# deepshark_power_sch.net
KiCad netlist of a schematic drawn in Altium Designer
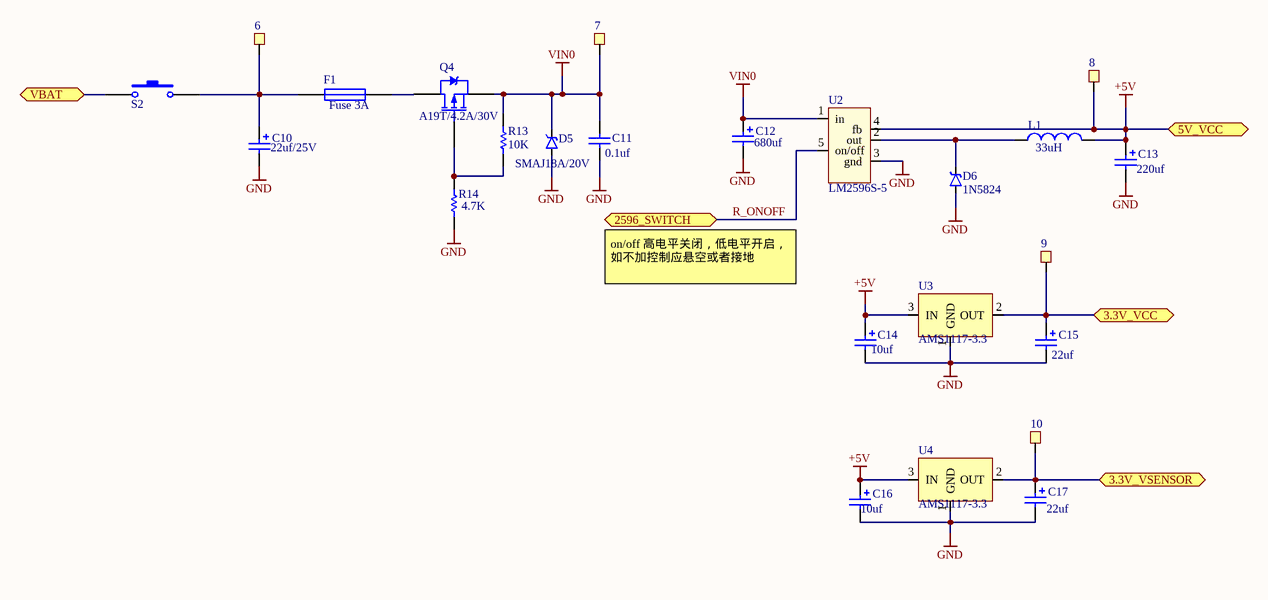
[diagram p0: deepshark_power_sch.SchDoc]

(export (version "E")
  (design (tool "Eeschema 10.0.6"))
  (components
    (comp (ref "6") (value "TP") (footprint "TestPoint") (libsource (lib "deepshark_sch_lib") (part "TP")))
    (comp (ref "7") (value "TP") (footprint "TestPoint") (libsource (lib "deepshark_sch_lib") (part "TP")))
    (comp (ref "8") (value "TP") (footprint "TestPoint") (libsource (lib "deepshark_sch_lib") (part "TP")))
    (comp (ref "9") (value "TP") (footprint "TestPoint") (libsource (lib "deepshark_sch_lib") (part "TP")))
    (comp (ref "10") (value "TP") (footprint "TestPoint") (libsource (lib "deepshark_sch_lib") (part "TP")))
    (comp (ref "C10")
      (value "22uf/25V")
      (footprint "22uf-25V")
      (description "Polarized Capacitor (Axial)")
      (fields (field (name "Comment") "Cap Pol2") (field (name "PUBLISHER") "Altium Limited"))
      (libsource (lib "Miscellaneous Devices") (part "Cap Pol2"))
    )
    (comp (ref "C11")
      (value "0.1uf")
      (footprint "6-0805_M")
      (description "Capacitor")
      (fields (field (name "Comment") "Cap") (field (name "PUBLISHER") "Altium Limited"))
      (libsource (lib "Miscellaneous Devices") (part "Cap"))
    )
    (comp (ref "C12")
      (value "680uf")
      (footprint "680uf-50v")
      (description "Polarized Capacitor (Axial)")
      (fields (field (name "Comment") "Cap Pol2") (field (name "PUBLISHER") "Altium Limited"))
      (libsource (lib "Miscellaneous Devices") (part "Cap Pol2"))
    )
    (comp (ref "C13")
      (value "220uf")
      (footprint "220uf-50v")
      (description "Polarized Capacitor (Axial)")
      (fields (field (name "Comment") "Cap Pol2") (field (name "PUBLISHER") "Altium Limited"))
      (libsource (lib "Miscellaneous Devices") (part "Cap Pol2"))
    )
    (comp (ref "C14")
      (value "10uf")
      (footprint "1206")
      (description "Polarized Capacitor (Axial)")
      (fields (field (name "Comment") "Cap Pol2") (field (name "PUBLISHER") "Altium Limited"))
      (libsource (lib "Miscellaneous Devices") (part "Cap Pol2"))
    )
    (comp (ref "C15")
      (value "22uf")
      (footprint "my0603")
      (description "Polarized Capacitor (Axial)")
      (fields (field (name "Comment") "Cap Pol2") (field (name "PUBLISHER") "Altium Limited"))
      (libsource (lib "Miscellaneous Devices") (part "Cap Pol2"))
    )
    (comp (ref "C16")
      (value "10uf")
      (footprint "1206")
      (description "Polarized Capacitor (Axial)")
      (fields (field (name "Comment") "Cap Pol2") (field (name "PUBLISHER") "Altium Limited"))
      (libsource (lib "Miscellaneous Devices") (part "Cap Pol2"))
    )
    (comp (ref "C17")
      (value "22uf")
      (footprint "my0603")
      (description "Polarized Capacitor (Axial)")
      (fields (field (name "Comment") "Cap Pol2") (field (name "PUBLISHER") "Altium Limited"))
      (libsource (lib "Miscellaneous Devices") (part "Cap Pol2"))
    )
    (comp (ref "D5") (value "SMAJ18A/20V") (footprint "SMBJ6.5A") (libsource (lib "常用2") (part "DW")))
    (comp (ref "D6") (value "1N5824") (footprint "1N5824") (libsource (lib "常用2") (part "DW")))
    (comp (ref "F1")
      (value "Fuse 3A")
      (footprint "1206")
      (description "Fuse")
      (fields (field (name "PUBLISHER") "Altium Limited"))
      (libsource (lib "Miscellaneous Devices") (part "Fuse 1"))
    )
    (comp (ref "L1")
      (value "33uH")
      (footprint "12x12 L")
      (description "Inductor")
      (fields (field (name "PUBLISHER") "Altium Limited"))
      (libsource (lib "Miscellaneous Devices") (part "Inductor"))
    )
    (comp (ref "Q4")
      (value "A19T/4.2A/30V")
      (footprint "A19T")
      (description "P-Channel Power MOSFET")
      (fields (field (name "PUBLISHER") "Altium Limited"))
      (libsource (lib "Miscellaneous Devices") (part "PMOS-2"))
    )
    (comp (ref "R13")
      (value "10K")
      (footprint "6-0805_M")
      (description "Resistor")
      (fields (field (name "Comment") "Res1") (field (name "PUBLISHER") "Altium Limited"))
      (libsource (lib "Miscellaneous Devices") (part "Res1"))
    )
    (comp (ref "R14")
      (value "4.7K")
      (footprint "6-0805_M")
      (description "Resistor")
      (fields (field (name "Comment") "Res1") (field (name "PUBLISHER") "Altium Limited"))
      (libsource (lib "Miscellaneous Devices") (part "Res1"))
    )
    (comp (ref "S2")
      (value "SW-PB")
      (footprint "switch-2bit")
      (description "Switch")
      (fields (field (name "PUBLISHER") "Altium Limited"))
      (libsource (lib "Miscellaneous Devices") (part "SW-PB"))
    )
    (comp (ref "U2")
      (value "LM2596S-5")
      (footprint "LM2596")
      (libsource (lib "buoys_sch_lib") (part "LM2596S-5"))
    )
    (comp (ref "U3")
      (value "AMS1117-3.3")
      (footprint "SOT223_M")
      (libsource (lib "buoys_sch_lib") (part "AMS1117-3.3"))
    )
    (comp (ref "U4")
      (value "AMS1117-3.3")
      (footprint "SOT223_M")
      (libsource (lib "buoys_sch_lib") (part "AMS1117-3.3"))
    )
  )
  (nets
    (net (code "1") (name "+5V") (class "Default")
      (node (ref "8") (pin "1") (pinfunction "1_1") (pintype "passive"))
      (node (ref "C13") (pin "1") (pinfunction "1_1") (pintype "passive"))
      (node (ref "C14") (pin "1") (pinfunction "1_1") (pintype "passive"))
      (node (ref "C16") (pin "1") (pinfunction "1_1") (pintype "passive"))
      (node (ref "L1") (pin "2") (pinfunction "2_2") (pintype "passive"))
      (node (ref "U2") (pin "4") (pinfunction "fb_4") (pintype "passive"))
      (node (ref "U3") (pin "3") (pinfunction "IN_3") (pintype "passive"))
      (node (ref "U4") (pin "3") (pinfunction "IN_3") (pintype "passive"))
    )
    (net (code "2") (name "/3.3V_VCC") (class "Default")
      (node (ref "9") (pin "1") (pinfunction "1_1") (pintype "passive"))
      (node (ref "C15") (pin "1") (pinfunction "1_1") (pintype "passive"))
      (node (ref "U3") (pin "2") (pinfunction "OUT_2") (pintype "passive"))
    )
    (net (code "3") (name "/3.3V_VSENSOR") (class "Default")
      (node (ref "10") (pin "1") (pinfunction "1_1") (pintype "passive"))
      (node (ref "C17") (pin "1") (pinfunction "1_1") (pintype "passive"))
      (node (ref "U4") (pin "2") (pinfunction "OUT_2") (pintype "passive"))
    )
    (net (code "4") (name "/R_ONOFF") (class "Default")
      (node (ref "U2") (pin "5") (pinfunction "on/off_5") (pintype "passive"))
    )
    (net (code "5") (name "/VBAT") (class "Default")
      (node (ref "S2") (pin "2") (pinfunction "2_2") (pintype "passive"))
    )
    (net (code "6") (name "GND") (class "Default")
      (node (ref "C10") (pin "2") (pinfunction "2_2") (pintype "passive"))
      (node (ref "C11") (pin "1") (pinfunction "1_1") (pintype "passive"))
      (node (ref "C12") (pin "2") (pinfunction "2_2") (pintype "passive"))
      (node (ref "C13") (pin "2") (pinfunction "2_2") (pintype "passive"))
      (node (ref "C14") (pin "2") (pinfunction "2_2") (pintype "passive"))
      (node (ref "C15") (pin "2") (pinfunction "2_2") (pintype "passive"))
      (node (ref "C16") (pin "2") (pinfunction "2_2") (pintype "passive"))
      (node (ref "C17") (pin "2") (pinfunction "2_2") (pintype "passive"))
      (node (ref "D5") (pin "A") (pintype "passive"))
      (node (ref "D6") (pin "A") (pintype "passive"))
      (node (ref "R14") (pin "1") (pinfunction "1_1") (pintype "passive"))
      (node (ref "U2") (pin "3") (pinfunction "gnd_3") (pintype "passive"))
      (node (ref "U3") (pin "1") (pinfunction "GND_1") (pintype "passive"))
      (node (ref "U4") (pin "1") (pinfunction "GND_1") (pintype "passive"))
    )
    (net (code "7") (name "Net-(6-Pad1)") (class "Default")
      (node (ref "6") (pin "1") (pinfunction "1_1") (pintype "passive"))
      (node (ref "C10") (pin "1") (pinfunction "1_1") (pintype "passive"))
      (node (ref "F1") (pin "1") (pinfunction "1_1") (pintype "passive"))
      (node (ref "S2") (pin "1") (pinfunction "1_1") (pintype "passive"))
    )
    (net (code "8") (name "Net-(Q4-D)") (class "Default")
      (node (ref "F1") (pin "2") (pinfunction "2_2") (pintype "passive"))
      (node (ref "Q4") (pin "2") (pinfunction "D_2") (pintype "passive"))
    )
    (net (code "9") (name "Net-(Q4-G)") (class "Default")
      (node (ref "Q4") (pin "1") (pinfunction "G_1") (pintype "passive"))
      (node (ref "R13") (pin "2") (pinfunction "2_2") (pintype "passive"))
      (node (ref "R14") (pin "2") (pinfunction "2_2") (pintype "passive"))
    )
    (net (code "10") (name "Net-(U2-out)") (class "Default")
      (node (ref "D6") (pin "K") (pintype "passive"))
      (node (ref "L1") (pin "1") (pinfunction "1_1") (pintype "passive"))
      (node (ref "U2") (pin "2") (pinfunction "out_2") (pintype "passive"))
    )
    (net (code "11") (name "VIN0") (class "Default")
      (node (ref "7") (pin "1") (pinfunction "1_1") (pintype "passive"))
      (node (ref "C11") (pin "2") (pinfunction "2_2") (pintype "passive"))
      (node (ref "C12") (pin "1") (pinfunction "1_1") (pintype "passive"))
      (node (ref "D5") (pin "K") (pintype "passive"))
      (node (ref "Q4") (pin "3") (pinfunction "S_3") (pintype "passive"))
      (node (ref "R13") (pin "1") (pinfunction "1_1") (pintype "passive"))
      (node (ref "U2") (pin "1") (pinfunction "in_1") (pintype "passive"))
    )
  )
)
